# MCU.net
KiCad netlist of a schematic drawn in Altium Designer
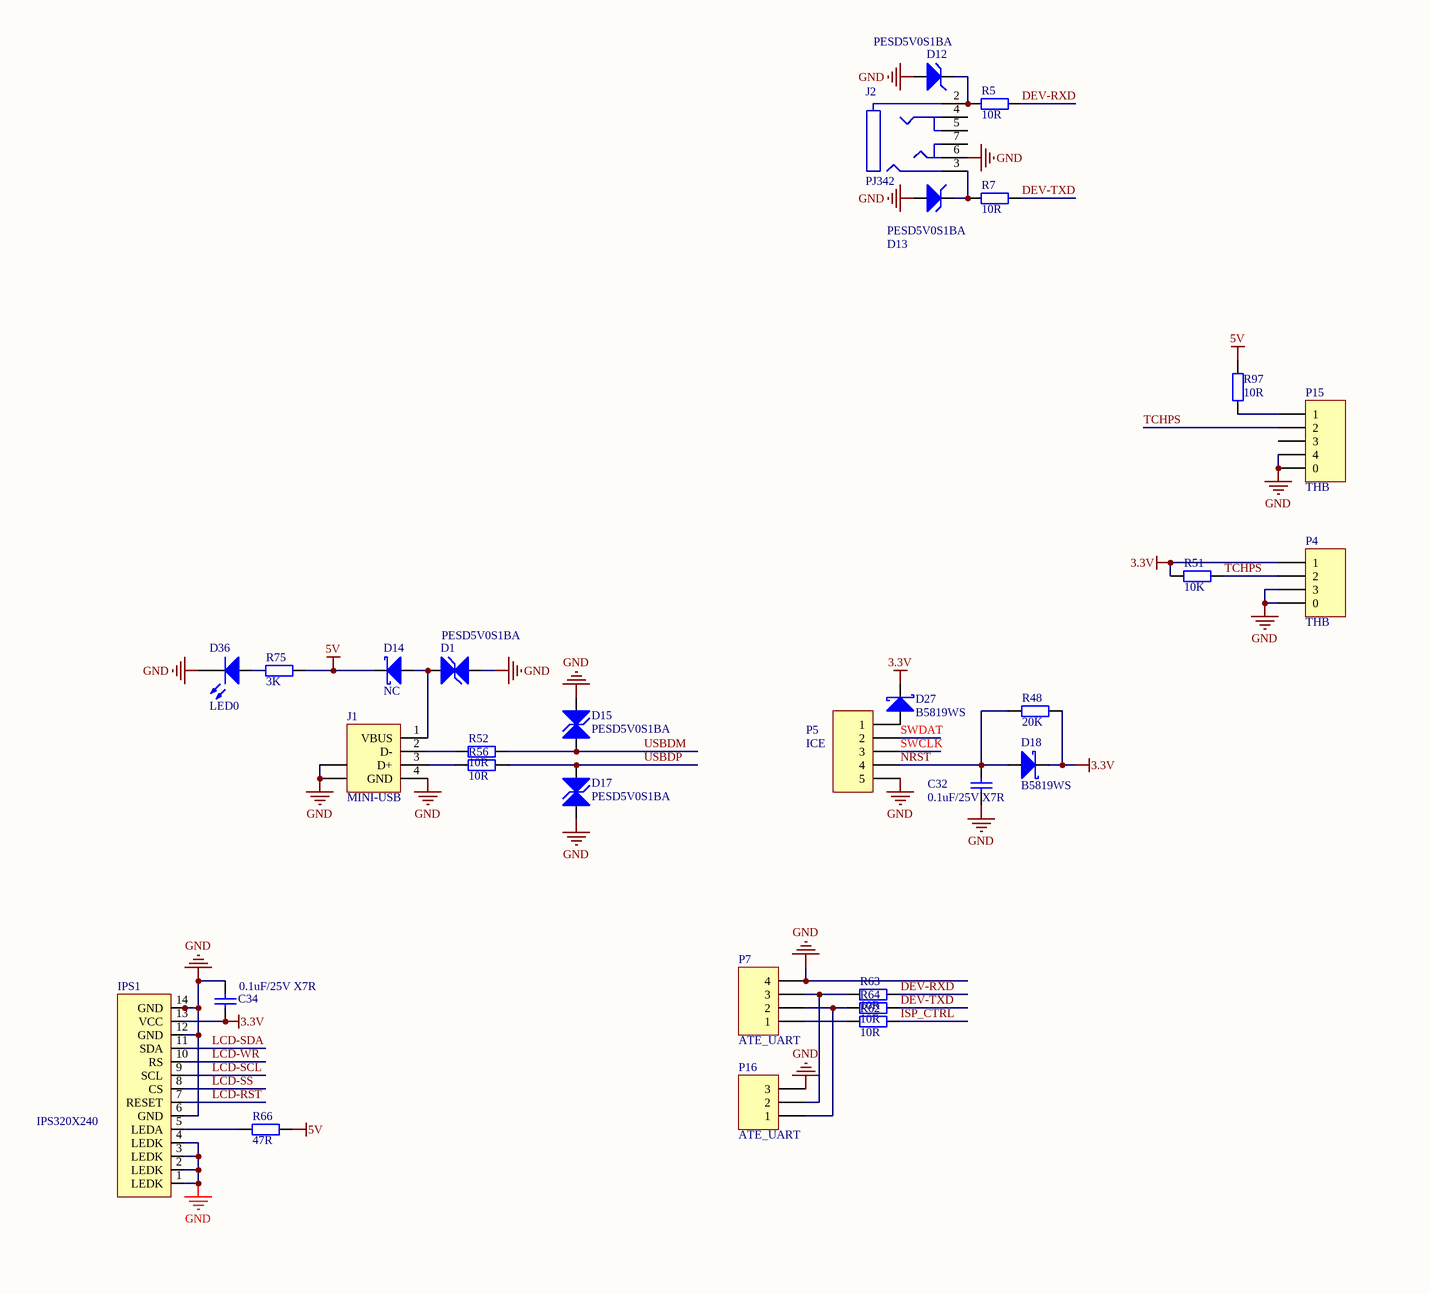
[diagram p0: MCU.SchDoc, left]
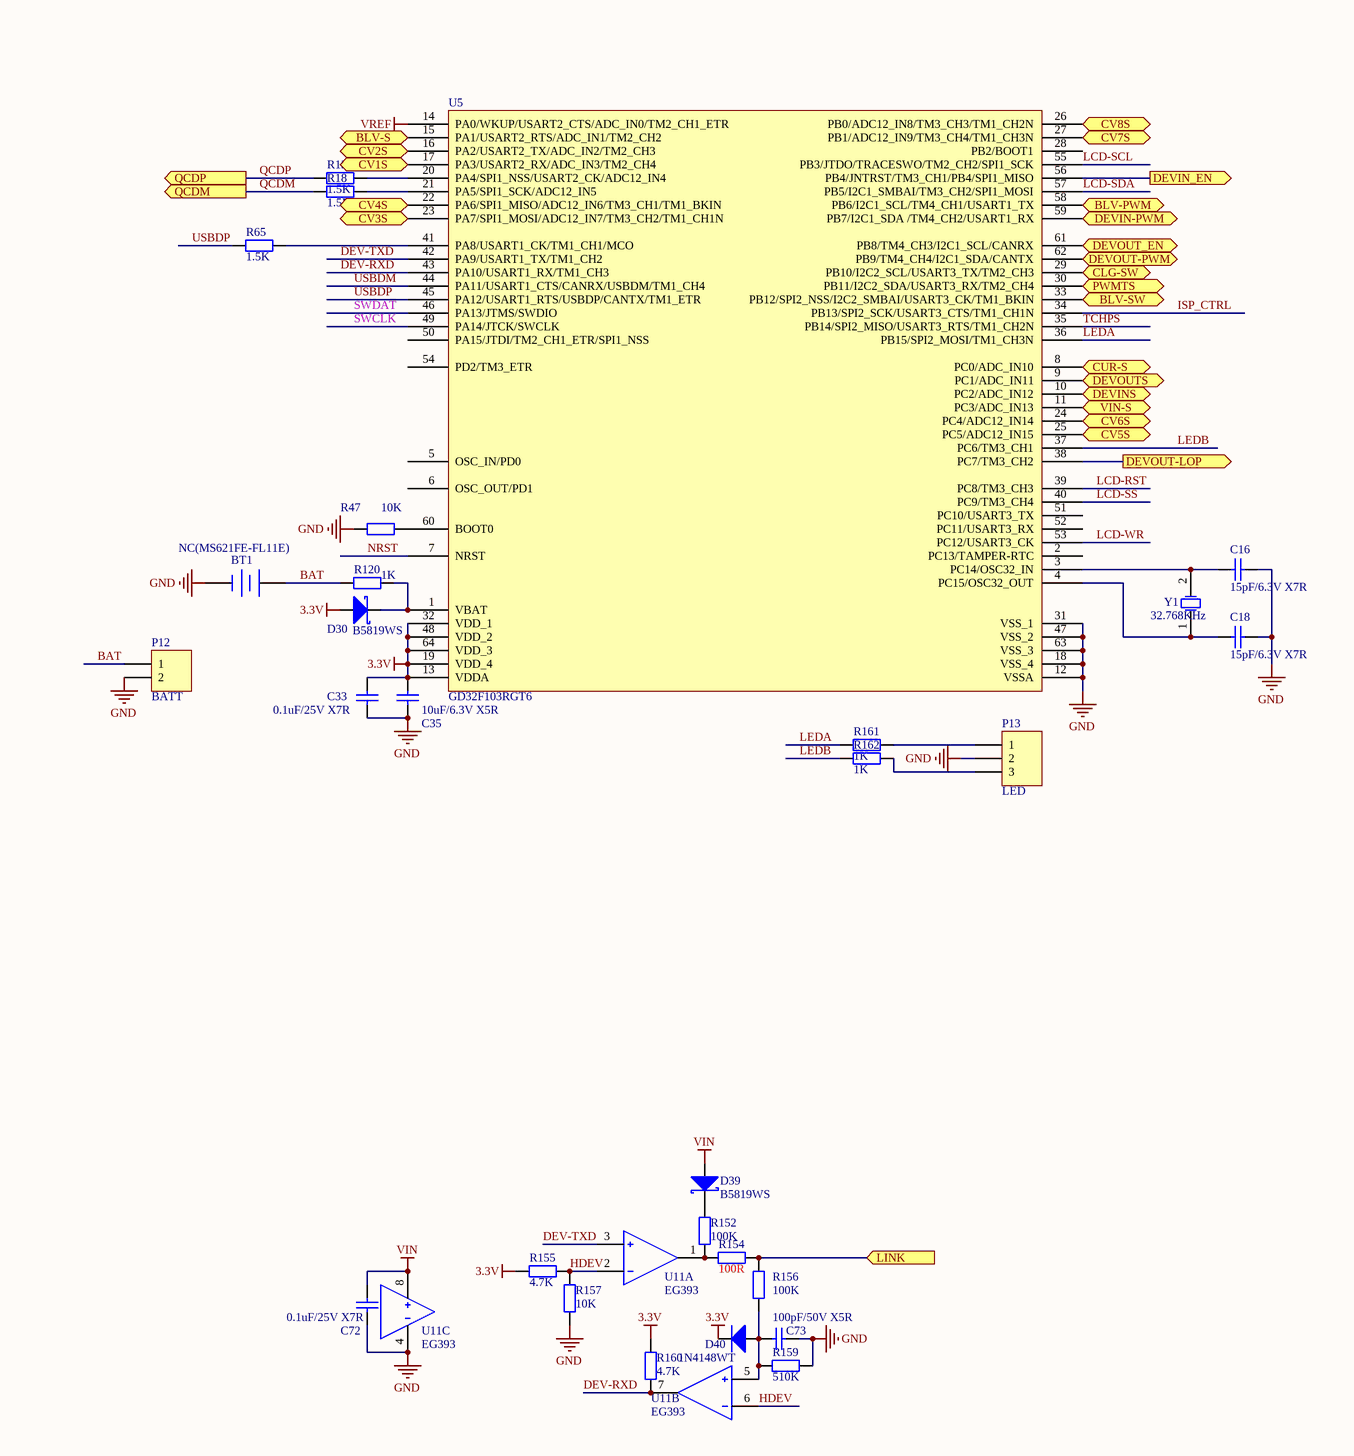
[diagram p1: MCU.SchDoc, right]

(export (version "E")
  (design (tool "Eeschema 10.0.6"))
  (components
    (comp (ref "BT1")
      (value "NC(MS621FE-FL11E)")
      (footprint "MS621FE FL11E")
      (description "Multicell Battery")
      (fields (field (name "PUBLISHER") "Altium Limited"))
      (libsource (lib "Miscellaneous Devices") (part "Battery"))
    )
    (comp (ref "C16")
      (value "15pF/6.3V X7R")
      (footprint "C-0603")
      (description "Capacitor")
      (fields (field (name "PUBLISHER") "Altium Limited"))
      (libsource (lib "Miscellaneous Devices") (part "Cap"))
    )
    (comp (ref "C18")
      (value "15pF/6.3V X7R")
      (footprint "C-0603")
      (description "Capacitor")
      (fields (field (name "PUBLISHER") "Altium Limited"))
      (libsource (lib "Miscellaneous Devices") (part "Cap"))
    )
    (comp (ref "C32")
      (value "0.1uF/25V X7R")
      (footprint "C-0603")
      (description "Capacitor")
      (fields (field (name "PUBLISHER") "Altium Limited"))
      (libsource (lib "Miscellaneous Devices") (part "Cap"))
    )
    (comp (ref "C33")
      (value "0.1uF/25V X7R")
      (footprint "C-0603")
      (description "Capacitor")
      (fields (field (name "PUBLISHER") "Altium Limited"))
      (libsource (lib "Miscellaneous Devices") (part "Cap"))
    )
    (comp (ref "C34")
      (value "0.1uF/25V X7R")
      (footprint "C-0603")
      (description "Capacitor")
      (fields (field (name "PUBLISHER") "Altium Limited"))
      (libsource (lib "Miscellaneous Devices") (part "Cap"))
    )
    (comp (ref "C35")
      (value "10uF/6.3V X5R")
      (footprint "C-0603")
      (description "Capacitor")
      (fields (field (name "PUBLISHER") "Altium Limited"))
      (libsource (lib "Miscellaneous Devices") (part "Cap"))
    )
    (comp (ref "C72")
      (value "0.1uF/25V X7R")
      (footprint "C-0603")
      (description "Capacitor")
      (fields (field (name "PUBLISHER") "Altium Limited"))
      (libsource (lib "Miscellaneous Devices") (part "Cap"))
    )
    (comp (ref "C73")
      (value "100pF/50V X5R")
      (footprint "C-0603")
      (description "Capacitor")
      (fields (field (name "PUBLISHER") "Altium Limited"))
      (libsource (lib "Miscellaneous Devices") (part "Cap"))
    )
    (comp (ref "D1") (value "PESD5V0S1BA") (footprint "SOD-323") (libsource (lib "ToboxStd") (part "TVS-D")))
    (comp (ref "D12")
      (value "PESD5V0S1BA")
      (footprint "SOD-323")
      (description "Zener Diode")
      (fields (field (name "PUBLISHER") "Altium Limited"))
      (libsource (lib "Miscellaneous Devices") (part "D Zener"))
    )
    (comp (ref "D13")
      (value "PESD5V0S1BA")
      (footprint "SOD-323")
      (description "Zener Diode")
      (fields (field (name "PUBLISHER") "Altium Limited"))
      (libsource (lib "Miscellaneous Devices") (part "D Zener"))
    )
    (comp (ref "D14")
      (value "NC")
      (footprint "SOD-323")
      (description "Schottky Diode")
      (fields
        (field (name "MANUFACTURER") "Generic Components")
        (field (name "PUBLISHER") "Altium Hobart Technology Centre")
      )
      (libsource (lib "Tobox") (part "D Schottky"))
    )
    (comp (ref "D15") (value "PESD5V0S1BA") (footprint "SOD-323") (libsource (lib "ToboxStd") (part "TVS-D")))
    (comp (ref "D17") (value "PESD5V0S1BA") (footprint "SOD-323") (libsource (lib "ToboxStd") (part "TVS-D")))
    (comp (ref "D18")
      (value "B5819WS")
      (footprint "SOD-323")
      (description "Schottky Diode")
      (fields (field (name "PUBLISHER") "Altium Limited"))
      (libsource (lib "Miscellaneous Devices") (part "D Schottky"))
    )
    (comp (ref "D27")
      (value "B5819WS")
      (footprint "SOD-323")
      (description "Schottky Diode")
      (fields
        (field (name "MANUFACTURER") "Generic Components")
        (field (name "PUBLISHER") "Altium Hobart Technology Centre")
      )
      (libsource (lib "Tobox") (part "D Schottky"))
    )
    (comp (ref "D30")
      (value "B5819WS")
      (footprint "SOD-323")
      (description "Schottky Diode")
      (fields (field (name "PUBLISHER") "Altium Limited"))
      (libsource (lib "Miscellaneous Devices") (part "D Schottky"))
    )
    (comp (ref "D36")
      (value "LED0")
      (footprint "LED-SMD-0603")
      (description "Typical INFRARED GaAs LED")
      (fields (field (name "PUBLISHER") "Altium Limited"))
      (libsource (lib "Miscellaneous Devices") (part "LED0"))
    )
    (comp (ref "D39")
      (value "B5819WS")
      (footprint "SOD-323")
      (description "Schottky Diode")
      (fields (field (name "PUBLISHER") "Altium Limited"))
      (libsource (lib "Miscellaneous Devices") (part "D Schottky"))
    )
    (comp (ref "D40")
      (value "1N4148WT")
      (footprint "SOD-323")
      (description "Default Diode")
      (fields (field (name "PUBLISHER") "Altium Limited"))
      (libsource (lib "Miscellaneous Devices") (part "Diode"))
    )
    (comp (ref "IPS1")
      (value "IPS320X240")
      (footprint "0.5K-AS-NPWB-14P")
      (libsource (lib "Tobox_in") (part "IPS320X240-14"))
    )
    (comp (ref "J1")
      (value "MINI-USB")
      (footprint "USB-MINI-C")
      (description "USB 1.1, Right Angle, Thru-Hole, Series A, Reverse Type, Receptacle, 4 Position, Black")
      (fields (field (name "PUBLISHER") "Altium Limited"))
      (libsource (lib "AMP Serial Bus USB") (part "440314-1"))
    )
    (comp (ref "J2") (value "PJ342") (footprint "PJ342") (libsource (lib "ToboxStd") (part "PJ342")))
    (comp (ref "P4")
      (value "THB")
      (footprint "1.25T-3P-SMT")
      (description "Header, 4-Pin")
      (fields (field (name "PUBLISHER") "Altium Limited"))
      (libsource (lib "") (part "Header 4_1"))
    )
    (comp (ref "P5")
      (value "ICE")
      (footprint "1.25T-5P")
      (description "Header, 5-Pin")
      (fields (field (name "PUBLISHER") "Altium Limited"))
      (libsource (lib "") (part "Header 5_1"))
    )
    (comp (ref "P7")
      (value "ATE_UART")
      (footprint "XH 2.54-4P")
      (description "Header, 4-Pin")
      (fields (field (name "PUBLISHER") "Altium Limited"))
      (libsource (lib "Miscellaneous Connectors") (part "Header 4"))
    )
    (comp (ref "P12")
      (value "BATT")
      (footprint "PH-2A")
      (description "Header, 2-Pin")
      (fields (field (name "PUBLISHER") "Altium Limited"))
      (libsource (lib "Miscellaneous Connectors") (part "Header 2"))
    )
    (comp (ref "P13")
      (value "LED")
      (footprint "HDR1X3")
      (description "共阴双色LED")
      (fields (field (name "PUBLISHER") "Altium Limited"))
      (libsource (lib "") (part "Header 3_1"))
    )
    (comp (ref "P15")
      (value "THB")
      (footprint "1.25T-4P-SMT")
      (description "Header, 5-Pin")
      (fields (field (name "PUBLISHER") "Altium Limited"))
      (libsource (lib "Miscellaneous Connectors") (part "Header 5"))
    )
    (comp (ref "P16")
      (value "ATE_UART")
      (footprint "XH 2.54-3P")
      (description "Header, 3-Pin")
      (fields (field (name "PUBLISHER") "Altium Limited"))
      (libsource (lib "Miscellaneous Connectors") (part "Header 3"))
    )
    (comp (ref "R5")
      (value "10R")
      (footprint "R-0603")
      (description "Resistor")
      (fields (field (name "PUBLISHER") "Altium Limited"))
      (libsource (lib "") (part "Res2_1"))
    )
    (comp (ref "R7")
      (value "10R")
      (footprint "R-0603")
      (description "Resistor")
      (fields (field (name "PUBLISHER") "Altium Limited"))
      (libsource (lib "Miscellaneous Devices") (part "Res2"))
    )
    (comp (ref "R13")
      (value "1.5K")
      (footprint "R-0603")
      (description "Resistor")
      (fields (field (name "PUBLISHER") "Altium Limited"))
      (libsource (lib "") (part "Res2_1"))
    )
    (comp (ref "R18")
      (value "1.5K")
      (footprint "R-0603")
      (description "Resistor")
      (fields (field (name "PUBLISHER") "Altium Limited"))
      (libsource (lib "") (part "Res2_1"))
    )
    (comp (ref "R47")
      (value "10K")
      (footprint "R-0603")
      (description "Resistor")
      (fields (field (name "PUBLISHER") "Altium Limited"))
      (libsource (lib "") (part "Res2_1"))
    )
    (comp (ref "R48")
      (value "20K")
      (footprint "R-0603")
      (description "Resistor")
      (fields (field (name "PUBLISHER") "Altium Limited"))
      (libsource (lib "") (part "Res2_1"))
    )
    (comp (ref "R51")
      (value "10K")
      (footprint "R-0603")
      (description "Resistor")
      (fields (field (name "PUBLISHER") "Altium Limited"))
      (libsource (lib "") (part "Res2_1"))
    )
    (comp (ref "R52")
      (value "10R")
      (footprint "R-0603")
      (description "Resistor")
      (fields (field (name "PUBLISHER") "Altium Limited"))
      (libsource (lib "") (part "Res2_1"))
    )
    (comp (ref "R56")
      (value "10R")
      (footprint "R-0603")
      (description "Resistor")
      (fields (field (name "PUBLISHER") "Altium Limited"))
      (libsource (lib "") (part "Res2_1"))
    )
    (comp (ref "R62")
      (value "10R")
      (footprint "R-0603")
      (description "Resistor")
      (fields (field (name "PUBLISHER") "Altium Limited"))
      (libsource (lib "") (part "Res2_1"))
    )
    (comp (ref "R63")
      (value "10R")
      (footprint "R-0603")
      (description "Resistor")
      (fields (field (name "PUBLISHER") "Altium Limited"))
      (libsource (lib "") (part "Res2_1"))
    )
    (comp (ref "R64")
      (value "10R")
      (footprint "R-0603")
      (description "Resistor")
      (fields (field (name "PUBLISHER") "Altium Limited"))
      (libsource (lib "") (part "Res2_1"))
    )
    (comp (ref "R65")
      (value "1.5K")
      (footprint "R-0603")
      (description "Resistor")
      (fields (field (name "PUBLISHER") "Altium Limited"))
      (libsource (lib "Miscellaneous Devices") (part "Res2"))
    )
    (comp (ref "R66")
      (value "47R")
      (footprint "R-0805")
      (description "Resistor")
      (fields (field (name "PUBLISHER") "Altium Limited"))
      (libsource (lib "Miscellaneous Devices") (part "Res2"))
    )
    (comp (ref "R75")
      (value "3K")
      (footprint "R-0603")
      (description "Resistor")
      (fields (field (name "PUBLISHER") "Altium Limited"))
      (libsource (lib "") (part "Res2_1"))
    )
    (comp (ref "R97")
      (value "10R")
      (footprint "R-0603")
      (description "Resistor")
      (fields (field (name "PUBLISHER") "Altium Limited"))
      (libsource (lib "Miscellaneous Devices") (part "Res2"))
    )
    (comp (ref "R120")
      (value "1K")
      (footprint "R-0603")
      (description "Resistor")
      (fields (field (name "PUBLISHER") "Altium Limited"))
      (libsource (lib "") (part "Res2_1"))
    )
    (comp (ref "R152")
      (value "100K")
      (footprint "R-0603")
      (description "Resistor")
      (fields (field (name "PUBLISHER") "Altium Limited"))
      (libsource (lib "") (part "Res2_1"))
    )
    (comp (ref "R154")
      (value "100R")
      (footprint "R-0603")
      (description "Resistor")
      (fields (field (name "PUBLISHER") "Altium Limited"))
      (libsource (lib "") (part "Res2_1"))
    )
    (comp (ref "R155")
      (value "4.7K")
      (footprint "R-0603")
      (description "Resistor")
      (fields (field (name "PUBLISHER") "Altium Limited"))
      (libsource (lib "") (part "Res2_1"))
    )
    (comp (ref "R156")
      (value "100K")
      (footprint "R-0603")
      (description "Resistor")
      (fields (field (name "PUBLISHER") "Altium Limited"))
      (libsource (lib "") (part "Res2_3"))
    )
    (comp (ref "R157")
      (value "10K")
      (footprint "R-0603")
      (description "Resistor")
      (fields (field (name "PUBLISHER") "Altium Limited"))
      (libsource (lib "") (part "Res2_2"))
    )
    (comp (ref "R159")
      (value "510K")
      (footprint "R-0603")
      (description "Resistor")
      (fields (field (name "PUBLISHER") "Altium Limited"))
      (libsource (lib "") (part "Res2_1"))
    )
    (comp (ref "R160")
      (value "4.7K")
      (footprint "R-0603")
      (description "Resistor")
      (fields (field (name "PUBLISHER") "Altium Limited"))
      (libsource (lib "") (part "Res2_2"))
    )
    (comp (ref "R161")
      (value "1K")
      (footprint "R-0603")
      (description "Resistor")
      (fields (field (name "PUBLISHER") "Altium Limited"))
      (libsource (lib "") (part "Res2_1"))
    )
    (comp (ref "R162")
      (value "1K")
      (footprint "R-0603")
      (description "Resistor")
      (fields (field (name "PUBLISHER") "Altium Limited"))
      (libsource (lib "") (part "Res2_1"))
    )
    (comp (ref "U5")
      (value "GD32F103RGT6")
      (footprint "TSQFP50P1200X1200X160-64N")
      (description "STM32 ARM-based 32-bit MCU with 128 Kbytes Flash, 64-pin LQFP, Industrial Temperature")
      (fields (field (name "PUBLISHER") "*"))
      (libsource (lib "ToboxStd") (part "GD32F103RBT6"))
    )
    (comp (ref "U11") (value "EG393") (footprint "SOIC8") (libsource (lib "Tobox") (part "Dual_OPAMP")))
    (comp (ref "Y1")
      (value "32.768KHz")
      (footprint "DT-38")
      (description "Crystal Oscillator")
      (fields (field (name "PUBLISHER") "Altium Limited"))
      (libsource (lib "Miscellaneous Devices") (part "XTAL"))
    )
  )
  (nets
    (net (code "1") (name "/BAT") (class "Default")
      (node (ref "BT1") (pin "1") (pinfunction "+_1") (pintype "passive"))
      (node (ref "P12") (pin "1") (pinfunction "1_1") (pintype "passive"))
      (node (ref "R120") (pin "2") (pinfunction "2_2") (pintype "passive"))
    )
    (net (code "2") (name "/BLV-PWM") (class "Default")
      (node (ref "U5") (pin "58") (pinfunction "PB6/I2C1_SCL/TM4_CH1/USART1_TX_58") (pintype "passive"))
    )
    (net (code "3") (name "/BLV-S") (class "Default")
      (node (ref "U5") (pin "15") (pinfunction "PA1/USART2_RTS/ADC_IN1/TM2_CH2_15") (pintype "passive"))
    )
    (net (code "4") (name "/BLV-SW") (class "Default")
      (node (ref "U5") (pin "33") (pinfunction "PB12/SPI2_NSS/I2C2_SMBAI/USART3_CK/TM1_BKIN_33") (pintype "passive"))
    )
    (net (code "5") (name "/CLG-SW") (class "Default")
      (node (ref "U5") (pin "29") (pinfunction "PB10/I2C2_SCL/USART3_TX/TM2_CH3_29") (pintype "passive"))
    )
    (net (code "6") (name "/CUR-S") (class "Default")
      (node (ref "U5") (pin "8") (pinfunction "PC0/ADC_IN10_8") (pintype "passive"))
    )
    (net (code "7") (name "/CV1S") (class "Default")
      (node (ref "U5") (pin "17") (pinfunction "PA3/USART2_RX/ADC_IN3/TM2_CH4_17") (pintype "passive"))
    )
    (net (code "8") (name "/CV2S") (class "Default")
      (node (ref "U5") (pin "16") (pinfunction "PA2/USART2_TX/ADC_IN2/TM2_CH3_16") (pintype "passive"))
    )
    (net (code "9") (name "/CV3S") (class "Default")
      (node (ref "U5") (pin "23") (pinfunction "PA7/SPI1_MOSI/ADC12_IN7/TM3_CH2/TM1_CH1N_23") (pintype "passive"))
    )
    (net (code "10") (name "/CV4S") (class "Default")
      (node (ref "U5") (pin "22") (pinfunction "PA6/SPI1_MISO/ADC12_IN6/TM3_CH1/TM1_BKIN_22") (pintype "passive"))
    )
    (net (code "11") (name "/CV5S") (class "Default")
      (node (ref "U5") (pin "25") (pinfunction "PC5/ADC12_IN15_25") (pintype "passive"))
    )
    (net (code "12") (name "/CV6S") (class "Default")
      (node (ref "U5") (pin "24") (pinfunction "PC4/ADC12_IN14_24") (pintype "passive"))
    )
    (net (code "13") (name "/CV7S") (class "Default")
      (node (ref "U5") (pin "27") (pinfunction "PB1/ADC12_IN9/TM3_CH4/TM1_CH3N_27") (pintype "passive"))
    )
    (net (code "14") (name "/CV8S") (class "Default")
      (node (ref "U5") (pin "26") (pinfunction "PB0/ADC12_IN8/TM3_CH3/TM1_CH2N_26") (pintype "passive"))
    )
    (net (code "15") (name "/DEV-RXD") (class "Default")
      (node (ref "R160") (pin "1") (pinfunction "1_1") (pintype "passive"))
      (node (ref "R5") (pin "1") (pinfunction "1_1") (pintype "passive"))
      (node (ref "R63") (pin "1") (pinfunction "1_1") (pintype "passive"))
      (node (ref "U11") (pin "7") (pinfunction "7_7") (pintype "passive"))
      (node (ref "U5") (pin "43") (pinfunction "PA10/USART1_RX/TM1_CH3_43") (pintype "passive"))
    )
    (net (code "16") (name "/DEV-TXD") (class "Default")
      (node (ref "R64") (pin "1") (pinfunction "1_1") (pintype "passive"))
      (node (ref "R7") (pin "2") (pinfunction "2_2") (pintype "passive"))
      (node (ref "U11") (pin "3") (pinfunction "3_3") (pintype "passive"))
      (node (ref "U5") (pin "42") (pinfunction "PA9/USART1_TX/TM1_CH2_42") (pintype "passive"))
    )
    (net (code "17") (name "/DEVIN-PWM") (class "Default")
      (node (ref "U5") (pin "59") (pinfunction "PB7/I2C1_SDA_/TM4_CH2/USART1_RX_59") (pintype "passive"))
    )
    (net (code "18") (name "/DEVINS") (class "Default")
      (node (ref "U5") (pin "10") (pinfunction "PC2/ADC_IN12_10") (pintype "passive"))
    )
    (net (code "19") (name "/DEVIN_EN") (class "Default")
      (node (ref "U5") (pin "56") (pinfunction "PB4/JNTRST/TM3_CH1/PB4/SPI1_MISO_56") (pintype "passive"))
    )
    (net (code "20") (name "/DEVOUT-LOP") (class "Default")
      (node (ref "U5") (pin "38") (pinfunction "PC7/TM3_CH2_38") (pintype "passive"))
    )
    (net (code "21") (name "/DEVOUT-PWM") (class "Default")
      (node (ref "U5") (pin "62") (pinfunction "PB9/TM4_CH4/I2C1_SDA/CANTX_62") (pintype "passive"))
    )
    (net (code "22") (name "/DEVOUTS") (class "Default")
      (node (ref "U5") (pin "9") (pinfunction "PC1/ADC_IN11_9") (pintype "passive"))
    )
    (net (code "23") (name "/DEVOUT_EN") (class "Default")
      (node (ref "U5") (pin "61") (pinfunction "PB8/TM4_CH3/I2C1_SCL/CANRX_61") (pintype "passive"))
    )
    (net (code "24") (name "/HDEV") (class "Default")
      (node (ref "R155") (pin "1") (pinfunction "1_1") (pintype "passive"))
      (node (ref "R157") (pin "2") (pinfunction "2_2") (pintype "passive"))
      (node (ref "U11") (pin "2") (pinfunction "2_2") (pintype "passive"))
      (node (ref "U11") (pin "6") (pinfunction "6_6") (pintype "passive"))
    )
    (net (code "25") (name "/ISP_CTRL") (class "Default")
      (node (ref "R62") (pin "1") (pinfunction "1_1") (pintype "passive"))
      (node (ref "U5") (pin "34") (pinfunction "PB13/SPI2_SCK/USART3_CTS/TM1_CH1N_34") (pintype "passive"))
    )
    (net (code "26") (name "/LCD-RST") (class "Default")
      (node (ref "IPS1") (pin "7") (pinfunction "RESET_7") (pintype "passive"))
      (node (ref "U5") (pin "39") (pinfunction "PC8/TM3_CH3_39") (pintype "passive"))
    )
    (net (code "27") (name "/LCD-SCL") (class "Default")
      (node (ref "IPS1") (pin "9") (pinfunction "SCL_9") (pintype "passive"))
      (node (ref "U5") (pin "55") (pinfunction "PB3/JTDO/TRACESWO/TM2_CH2/SPI1_SCK_55") (pintype "passive"))
    )
    (net (code "28") (name "/LCD-SDA") (class "Default")
      (node (ref "IPS1") (pin "11") (pinfunction "SDA_11") (pintype "passive"))
      (node (ref "U5") (pin "57") (pinfunction "PB5/I2C1_SMBAI/TM3_CH2/SPI1_MOSI_57") (pintype "passive"))
    )
    (net (code "29") (name "/LCD-SS") (class "Default")
      (node (ref "IPS1") (pin "8") (pinfunction "CS_8") (pintype "passive"))
      (node (ref "U5") (pin "40") (pinfunction "PC9/TM3_CH4_40") (pintype "passive"))
    )
    (net (code "30") (name "/LCD-WR") (class "Default")
      (node (ref "IPS1") (pin "10") (pinfunction "RS_10") (pintype "passive"))
      (node (ref "U5") (pin "53") (pinfunction "PC12/USART3_CK_53") (pintype "passive"))
    )
    (net (code "31") (name "/LEDA") (class "Default")
      (node (ref "R161") (pin "2") (pinfunction "2_2") (pintype "passive"))
      (node (ref "U5") (pin "36") (pinfunction "PB15/SPI2_MOSI/TM1_CH3N_36") (pintype "passive"))
    )
    (net (code "32") (name "/LEDB") (class "Default")
      (node (ref "R162") (pin "2") (pinfunction "2_2") (pintype "passive"))
      (node (ref "U5") (pin "37") (pinfunction "PC6/TM3_CH1_37") (pintype "passive"))
    )
    (net (code "33") (name "/LINK") (class "Default")
      (node (ref "R154") (pin "1") (pinfunction "1_1") (pintype "passive"))
      (node (ref "R156") (pin "1") (pinfunction "1_1") (pintype "passive"))
    )
    (net (code "34") (name "/NRST") (class "Default")
      (node (ref "C32") (pin "1") (pinfunction "1_1") (pintype "passive"))
      (node (ref "D18") (pin "1") (pinfunction "A_1") (pintype "passive"))
      (node (ref "P5") (pin "4") (pinfunction "4_4") (pintype "passive"))
      (node (ref "R48") (pin "2") (pinfunction "2_2") (pintype "passive"))
      (node (ref "U5") (pin "7") (pinfunction "NRST_7") (pintype "passive"))
    )
    (net (code "35") (name "/PWMTS") (class "Default")
      (node (ref "U5") (pin "30") (pinfunction "PB11/I2C2_SDA/USART3_RX/TM2_CH4_30") (pintype "passive"))
    )
    (net (code "36") (name "/QCDM") (class "Default")
      (node (ref "R18") (pin "2") (pinfunction "2_2") (pintype "passive"))
    )
    (net (code "37") (name "/QCDP") (class "Default")
      (node (ref "R13") (pin "2") (pinfunction "2_2") (pintype "passive"))
    )
    (net (code "38") (name "/SWCLK") (class "Default")
      (node (ref "P5") (pin "3") (pinfunction "3_3") (pintype "passive"))
      (node (ref "U5") (pin "49") (pinfunction "PA14/JTCK/SWCLK_49") (pintype "passive"))
    )
    (net (code "39") (name "/SWDAT") (class "Default")
      (node (ref "P5") (pin "2") (pinfunction "2_2") (pintype "passive"))
      (node (ref "U5") (pin "46") (pinfunction "PA13/JTMS/SWDIO_46") (pintype "passive"))
    )
    (net (code "40") (name "/TCHPS") (class "Default")
      (node (ref "P15") (pin "2") (pinfunction "2_2") (pintype "passive"))
      (node (ref "P4") (pin "2") (pinfunction "2_2") (pintype "passive"))
      (node (ref "R51") (pin "1") (pinfunction "1_1") (pintype "passive"))
      (node (ref "U5") (pin "35") (pinfunction "PB14/SPI2_MISO/USART3_RTS/TM1_CH2N_35") (pintype "passive"))
    )
    (net (code "41") (name "/USBDM") (class "Default")
      (node (ref "D15") (pin "2") (pinfunction "2_2") (pintype "passive"))
      (node (ref "R52") (pin "1") (pinfunction "1_1") (pintype "passive"))
      (node (ref "U5") (pin "44") (pinfunction "PA11/USART1_CTS/CANRX/USBDM/TM1_CH4_44") (pintype "passive"))
    )
    (net (code "42") (name "/USBDP") (class "Default")
      (node (ref "D17") (pin "2") (pinfunction "2_2") (pintype "passive"))
      (node (ref "R56") (pin "1") (pinfunction "1_1") (pintype "passive"))
      (node (ref "R65") (pin "1") (pinfunction "1_1") (pintype "passive"))
      (node (ref "U5") (pin "45") (pinfunction "PA12/USART1_RTS/USBDP/CANTX/TM1_ETR_45") (pintype "passive"))
    )
    (net (code "43") (name "/VIN-S") (class "Default")
      (node (ref "U5") (pin "11") (pinfunction "PC3/ADC_IN13_11") (pintype "passive"))
    )
    (net (code "44") (name "3.3V") (class "Default")
      (node (ref "C33") (pin "2") (pinfunction "2_2") (pintype "passive"))
      (node (ref "C34") (pin "2") (pinfunction "2_2") (pintype "passive"))
      (node (ref "C35") (pin "2") (pinfunction "2_2") (pintype "passive"))
      (node (ref "D18") (pin "2") (pinfunction "K_2") (pintype "passive"))
      (node (ref "D27") (pin "2") (pinfunction "K_2") (pintype "passive"))
      (node (ref "D30") (pin "1") (pinfunction "A_1") (pintype "passive"))
      (node (ref "D40") (pin "2") (pinfunction "K_2") (pintype "passive"))
      (node (ref "IPS1") (pin "13") (pinfunction "VCC_13") (pintype "passive"))
      (node (ref "P4") (pin "1") (pinfunction "1_1") (pintype "passive"))
      (node (ref "R155") (pin "2") (pinfunction "2_2") (pintype "passive"))
      (node (ref "R160") (pin "2") (pinfunction "2_2") (pintype "passive"))
      (node (ref "R48") (pin "1") (pinfunction "1_1") (pintype "passive"))
      (node (ref "R51") (pin "2") (pinfunction "2_2") (pintype "passive"))
      (node (ref "U5") (pin "13") (pinfunction "VDDA_13") (pintype "passive"))
      (node (ref "U5") (pin "19") (pinfunction "VDD_4_19") (pintype "passive"))
      (node (ref "U5") (pin "32") (pinfunction "VDD_1_32") (pintype "passive"))
      (node (ref "U5") (pin "48") (pinfunction "VDD_2_48") (pintype "passive"))
      (node (ref "U5") (pin "64") (pinfunction "VDD_3_64") (pintype "passive"))
    )
    (net (code "45") (name "5V") (class "Default")
      (node (ref "D14") (pin "2") (pinfunction "K_2") (pintype "passive"))
      (node (ref "R66") (pin "2") (pinfunction "2_2") (pintype "passive"))
      (node (ref "R75") (pin "1") (pinfunction "1_1") (pintype "passive"))
      (node (ref "R97") (pin "2") (pinfunction "2_2") (pintype "passive"))
    )
    (net (code "46") (name "GND") (class "Default")
      (node (ref "BT1") (pin "2") (pinfunction "-_2") (pintype "passive"))
      (node (ref "C16") (pin "1") (pinfunction "1_1") (pintype "passive"))
      (node (ref "C18") (pin "1") (pinfunction "1_1") (pintype "passive"))
      (node (ref "C32") (pin "2") (pinfunction "2_2") (pintype "passive"))
      (node (ref "C33") (pin "1") (pinfunction "1_1") (pintype "passive"))
      (node (ref "C34") (pin "1") (pinfunction "1_1") (pintype "passive"))
      (node (ref "C35") (pin "1") (pinfunction "1_1") (pintype "passive"))
      (node (ref "C72") (pin "2") (pinfunction "2_2") (pintype "passive"))
      (node (ref "C73") (pin "1") (pinfunction "1_1") (pintype "passive"))
      (node (ref "D1") (pin "1") (pinfunction "1_1") (pintype "passive"))
      (node (ref "D12") (pin "1") (pinfunction "A_1") (pintype "passive"))
      (node (ref "D13") (pin "1") (pinfunction "A_1") (pintype "passive"))
      (node (ref "D15") (pin "1") (pinfunction "1_1") (pintype "passive"))
      (node (ref "D17") (pin "1") (pinfunction "1_1") (pintype "passive"))
      (node (ref "D36") (pin "2") (pinfunction "K_2") (pintype "passive"))
      (node (ref "IPS1") (pin "0") (pinfunction "0_0") (pintype "passive"))
      (node (ref "IPS1") (pin "1") (pinfunction "LEDK_1") (pintype "passive"))
      (node (ref "IPS1") (pin "12") (pinfunction "GND_12") (pintype "passive"))
      (node (ref "IPS1") (pin "14") (pinfunction "GND_14") (pintype "passive"))
      (node (ref "IPS1") (pin "2") (pinfunction "LEDK_2") (pintype "passive"))
      (node (ref "IPS1") (pin "3") (pinfunction "LEDK_3") (pintype "passive"))
      (node (ref "IPS1") (pin "4") (pinfunction "LEDK_4") (pintype "passive"))
      (node (ref "IPS1") (pin "6") (pinfunction "GND_6") (pintype "passive"))
      (node (ref "J1") (pin "4") (pinfunction "GND_4") (pintype "passive"))
      (node (ref "J1") (pin "5") (pinfunction "SHLD_5") (pintype "passive"))
      (node (ref "J1") (pin "6") (pinfunction "SHLD_6") (pintype "passive"))
      (node (ref "J2") (pin "6") (pinfunction "6_6") (pintype "passive"))
      (node (ref "P12") (pin "2") (pinfunction "2_2") (pintype "passive"))
      (node (ref "P13") (pin "2") (pinfunction "2_2") (pintype "passive"))
      (node (ref "P15") (pin "0") (pinfunction "0_0") (pintype "passive"))
      (node (ref "P15") (pin "4") (pinfunction "4_4") (pintype "passive"))
      (node (ref "P16") (pin "3") (pinfunction "3_3") (pintype "passive"))
      (node (ref "P4") (pin "0") (pinfunction "0_0") (pintype "passive"))
      (node (ref "P4") (pin "3") (pinfunction "3_3") (pintype "passive"))
      (node (ref "P5") (pin "5") (pinfunction "5_5") (pintype "passive"))
      (node (ref "P7") (pin "4") (pinfunction "4_4") (pintype "passive"))
      (node (ref "R157") (pin "1") (pinfunction "1_1") (pintype "passive"))
      (node (ref "R159") (pin "1") (pinfunction "1_1") (pintype "passive"))
      (node (ref "R47") (pin "2") (pinfunction "2_2") (pintype "passive"))
      (node (ref "U11") (pin "4") (pinfunction "4_4") (pintype "passive"))
      (node (ref "U5") (pin "12") (pinfunction "VSSA_12") (pintype "passive"))
      (node (ref "U5") (pin "18") (pinfunction "VSS_4_18") (pintype "passive"))
      (node (ref "U5") (pin "31") (pinfunction "VSS_1_31") (pintype "passive"))
      (node (ref "U5") (pin "47") (pinfunction "VSS_2_47") (pintype "passive"))
      (node (ref "U5") (pin "63") (pinfunction "VSS_3_63") (pintype "passive"))
    )
    (net (code "47") (name "Net-(D12-K)") (class "Default")
      (node (ref "D12") (pin "2") (pinfunction "K_2") (pintype "passive"))
      (node (ref "J2") (pin "2") (pinfunction "2_2") (pintype "passive"))
      (node (ref "R5") (pin "2") (pinfunction "2_2") (pintype "passive"))
    )
    (net (code "48") (name "Net-(D13-K)") (class "Default")
      (node (ref "D13") (pin "2") (pinfunction "K_2") (pintype "passive"))
      (node (ref "J2") (pin "3") (pinfunction "3_3") (pintype "passive"))
      (node (ref "R7") (pin "1") (pinfunction "1_1") (pintype "passive"))
    )
    (net (code "49") (name "Net-(D14-A)") (class "Default")
      (node (ref "D1") (pin "2") (pinfunction "2_2") (pintype "passive"))
      (node (ref "D14") (pin "1") (pinfunction "A_1") (pintype "passive"))
      (node (ref "J1") (pin "1") (pinfunction "VBUS_1") (pintype "passive"))
    )
    (net (code "50") (name "Net-(D27-A)") (class "Default")
      (node (ref "D27") (pin "1") (pinfunction "A_1") (pintype "passive"))
      (node (ref "P5") (pin "1") (pinfunction "1_1") (pintype "passive"))
    )
    (net (code "51") (name "Net-(D30-K)") (class "Default")
      (node (ref "D30") (pin "2") (pinfunction "K_2") (pintype "passive"))
      (node (ref "R120") (pin "1") (pinfunction "1_1") (pintype "passive"))
      (node (ref "U5") (pin "1") (pinfunction "VBAT_1") (pintype "passive"))
    )
    (net (code "52") (name "Net-(D36-A)") (class "Default")
      (node (ref "D36") (pin "1") (pinfunction "A_1") (pintype "passive"))
      (node (ref "R75") (pin "2") (pinfunction "2_2") (pintype "passive"))
    )
    (net (code "53") (name "Net-(D39-K)") (class "Default")
      (node (ref "D39") (pin "2") (pinfunction "K_2") (pintype "passive"))
      (node (ref "R152") (pin "1") (pinfunction "1_1") (pintype "passive"))
    )
    (net (code "54") (name "Net-(D40-A)") (class "Default")
      (node (ref "C73") (pin "2") (pinfunction "2_2") (pintype "passive"))
      (node (ref "D40") (pin "1") (pinfunction "A_1") (pintype "passive"))
      (node (ref "R156") (pin "2") (pinfunction "2_2") (pintype "passive"))
      (node (ref "R159") (pin "2") (pinfunction "2_2") (pintype "passive"))
      (node (ref "U11") (pin "5") (pinfunction "5_5") (pintype "passive"))
    )
    (net (code "55") (name "Net-(IPS1-LEDA)") (class "Default")
      (node (ref "IPS1") (pin "5") (pinfunction "LEDA_5") (pintype "passive"))
      (node (ref "R66") (pin "1") (pinfunction "1_1") (pintype "passive"))
    )
    (net (code "56") (name "Net-(J1-D+)") (class "Default")
      (node (ref "J1") (pin "3") (pinfunction "D+_3") (pintype "passive"))
      (node (ref "R56") (pin "2") (pinfunction "2_2") (pintype "passive"))
    )
    (net (code "57") (name "Net-(J1-D-)") (class "Default")
      (node (ref "J1") (pin "2") (pinfunction "D-_2") (pintype "passive"))
      (node (ref "R52") (pin "2") (pinfunction "2_2") (pintype "passive"))
    )
    (net (code "58") (name "Net-(P7-Pad1)") (class "Default")
      (node (ref "P7") (pin "1") (pinfunction "1_1") (pintype "passive"))
      (node (ref "R62") (pin "2") (pinfunction "2_2") (pintype "passive"))
    )
    (net (code "59") (name "Net-(P13-Pad1)") (class "Default")
      (node (ref "P13") (pin "1") (pinfunction "1_1") (pintype "passive"))
      (node (ref "R161") (pin "1") (pinfunction "1_1") (pintype "passive"))
    )
    (net (code "60") (name "Net-(P13-Pad3)") (class "Default")
      (node (ref "P13") (pin "3") (pinfunction "3_3") (pintype "passive"))
      (node (ref "R162") (pin "1") (pinfunction "1_1") (pintype "passive"))
    )
    (net (code "61") (name "Net-(P15-Pad1)") (class "Default")
      (node (ref "P15") (pin "1") (pinfunction "1_1") (pintype "passive"))
      (node (ref "R97") (pin "1") (pinfunction "1_1") (pintype "passive"))
    )
    (net (code "62") (name "Net-(P16-Pad1)") (class "Default")
      (node (ref "P16") (pin "1") (pinfunction "1_1") (pintype "passive"))
      (node (ref "P7") (pin "2") (pinfunction "2_2") (pintype "passive"))
      (node (ref "R64") (pin "2") (pinfunction "2_2") (pintype "passive"))
    )
    (net (code "63") (name "Net-(P16-Pad2)") (class "Default")
      (node (ref "P16") (pin "2") (pinfunction "2_2") (pintype "passive"))
      (node (ref "P7") (pin "3") (pinfunction "3_3") (pintype "passive"))
      (node (ref "R63") (pin "2") (pinfunction "2_2") (pintype "passive"))
    )
    (net (code "64") (name "Net-(R152-Pad2)") (class "Default")
      (node (ref "R152") (pin "2") (pinfunction "2_2") (pintype "passive"))
      (node (ref "R154") (pin "2") (pinfunction "2_2") (pintype "passive"))
      (node (ref "U11") (pin "1") (pinfunction "1_1") (pintype "passive"))
    )
    (net (code "65") (name "Net-(U5-BOOT0)") (class "Default")
      (node (ref "R47") (pin "1") (pinfunction "1_1") (pintype "passive"))
      (node (ref "U5") (pin "60") (pinfunction "BOOT0_60") (pintype "passive"))
    )
    (net (code "66") (name "Net-(U5-PA4{slash}SPI1_NSS{slash}USART2_CK{slash}ADC12_IN4)") (class "Default")
      (node (ref "R13") (pin "1") (pinfunction "1_1") (pintype "passive"))
      (node (ref "U5") (pin "20") (pinfunction "PA4/SPI1_NSS/USART2_CK/ADC12_IN4_20") (pintype "passive"))
    )
    (net (code "67") (name "Net-(U5-PA5{slash}SPI1_SCK{slash}ADC12_IN5)") (class "Default")
      (node (ref "R18") (pin "1") (pinfunction "1_1") (pintype "passive"))
      (node (ref "U5") (pin "21") (pinfunction "PA5/SPI1_SCK/ADC12_IN5_21") (pintype "passive"))
    )
    (net (code "68") (name "Net-(U5-PA8{slash}USART1_CK{slash}TM1_CH1{slash}MCO)") (class "Default")
      (node (ref "R65") (pin "2") (pinfunction "2_2") (pintype "passive"))
      (node (ref "U5") (pin "41") (pinfunction "PA8/USART1_CK/TM1_CH1/MCO_41") (pintype "passive"))
    )
    (net (code "69") (name "Net-(U5-PC14{slash}OSC32_IN)") (class "Default")
      (node (ref "C16") (pin "2") (pinfunction "2_2") (pintype "passive"))
      (node (ref "U5") (pin "3") (pinfunction "PC14/OSC32_IN_3") (pintype "passive"))
      (node (ref "Y1") (pin "2") (pinfunction "OSC2_2") (pintype "passive"))
    )
    (net (code "70") (name "Net-(U5-PC15{slash}OSC32_OUT)") (class "Default")
      (node (ref "C18") (pin "2") (pinfunction "2_2") (pintype "passive"))
      (node (ref "U5") (pin "4") (pinfunction "PC15/OSC32_OUT_4") (pintype "passive"))
      (node (ref "Y1") (pin "1") (pinfunction "OSC1_1") (pintype "passive"))
    )
    (net (code "71") (name "VIN") (class "Default")
      (node (ref "C72") (pin "1") (pinfunction "1_1") (pintype "passive"))
      (node (ref "D39") (pin "1") (pinfunction "A_1") (pintype "passive"))
      (node (ref "U11") (pin "8") (pinfunction "8_8") (pintype "passive"))
    )
    (net (code "72") (name "VREF") (class "Default")
      (node (ref "U5") (pin "14") (pinfunction "PA0/WKUP/USART2_CTS/ADC_IN0/TM2_CH1_ETR_14") (pintype "passive"))
    )
    (net (code "73") (name "unconnected-(J2-Pad4)") (class "Default")
      (node (ref "J2") (pin "4") (pinfunction "4_4") (pintype "passive"))
    )
    (net (code "74") (name "unconnected-(J2-Pad5)") (class "Default")
      (node (ref "J2") (pin "5") (pinfunction "5_5") (pintype "passive"))
    )
    (net (code "75") (name "unconnected-(J2-Pad7)") (class "Default")
      (node (ref "J2") (pin "7") (pinfunction "7_7") (pintype "passive"))
    )
    (net (code "76") (name "unconnected-(P15-Pad3)") (class "Default")
      (node (ref "P15") (pin "3") (pinfunction "3_3") (pintype "passive"))
    )
    (net (code "77") (name "unconnected-(U5-OSC_IN{slash}PD0-Pad5)") (class "Default")
      (node (ref "U5") (pin "5") (pinfunction "OSC_IN/PD0_5") (pintype "passive"))
    )
    (net (code "78") (name "unconnected-(U5-OSC_OUT{slash}PD1-Pad6)") (class "Default")
      (node (ref "U5") (pin "6") (pinfunction "OSC_OUT/PD1_6") (pintype "passive"))
    )
    (net (code "79") (name "unconnected-(U5-PA15{slash}JTDI{slash}TM2_CH1_ETR{slash}SPI1_NSS-Pad50)") (class "Default")
      (node (ref "U5") (pin "50") (pinfunction "PA15/JTDI/TM2_CH1_ETR/SPI1_NSS_50") (pintype "passive"))
    )
    (net (code "80") (name "unconnected-(U5-PB2{slash}BOOT1-Pad28)") (class "Default")
      (node (ref "U5") (pin "28") (pinfunction "PB2/BOOT1_28") (pintype "passive"))
    )
    (net (code "81") (name "unconnected-(U5-PC10{slash}USART3_TX-Pad51)") (class "Default")
      (node (ref "U5") (pin "51") (pinfunction "PC10/USART3_TX_51") (pintype "passive"))
    )
    (net (code "82") (name "unconnected-(U5-PC11{slash}USART3_RX-Pad52)") (class "Default")
      (node (ref "U5") (pin "52") (pinfunction "PC11/USART3_RX_52") (pintype "passive"))
    )
    (net (code "83") (name "unconnected-(U5-PC13{slash}TAMPER-RTC-Pad2)") (class "Default")
      (node (ref "U5") (pin "2") (pinfunction "PC13/TAMPER-RTC_2") (pintype "passive"))
    )
    (net (code "84") (name "unconnected-(U5-PD2{slash}TM3_ETR-Pad54)") (class "Default")
      (node (ref "U5") (pin "54") (pinfunction "PD2/TM3_ETR_54") (pintype "passive"))
    )
  )
)
